# n64cart-1G.net
KiCad netlist of a schematic drawn in EAGLE
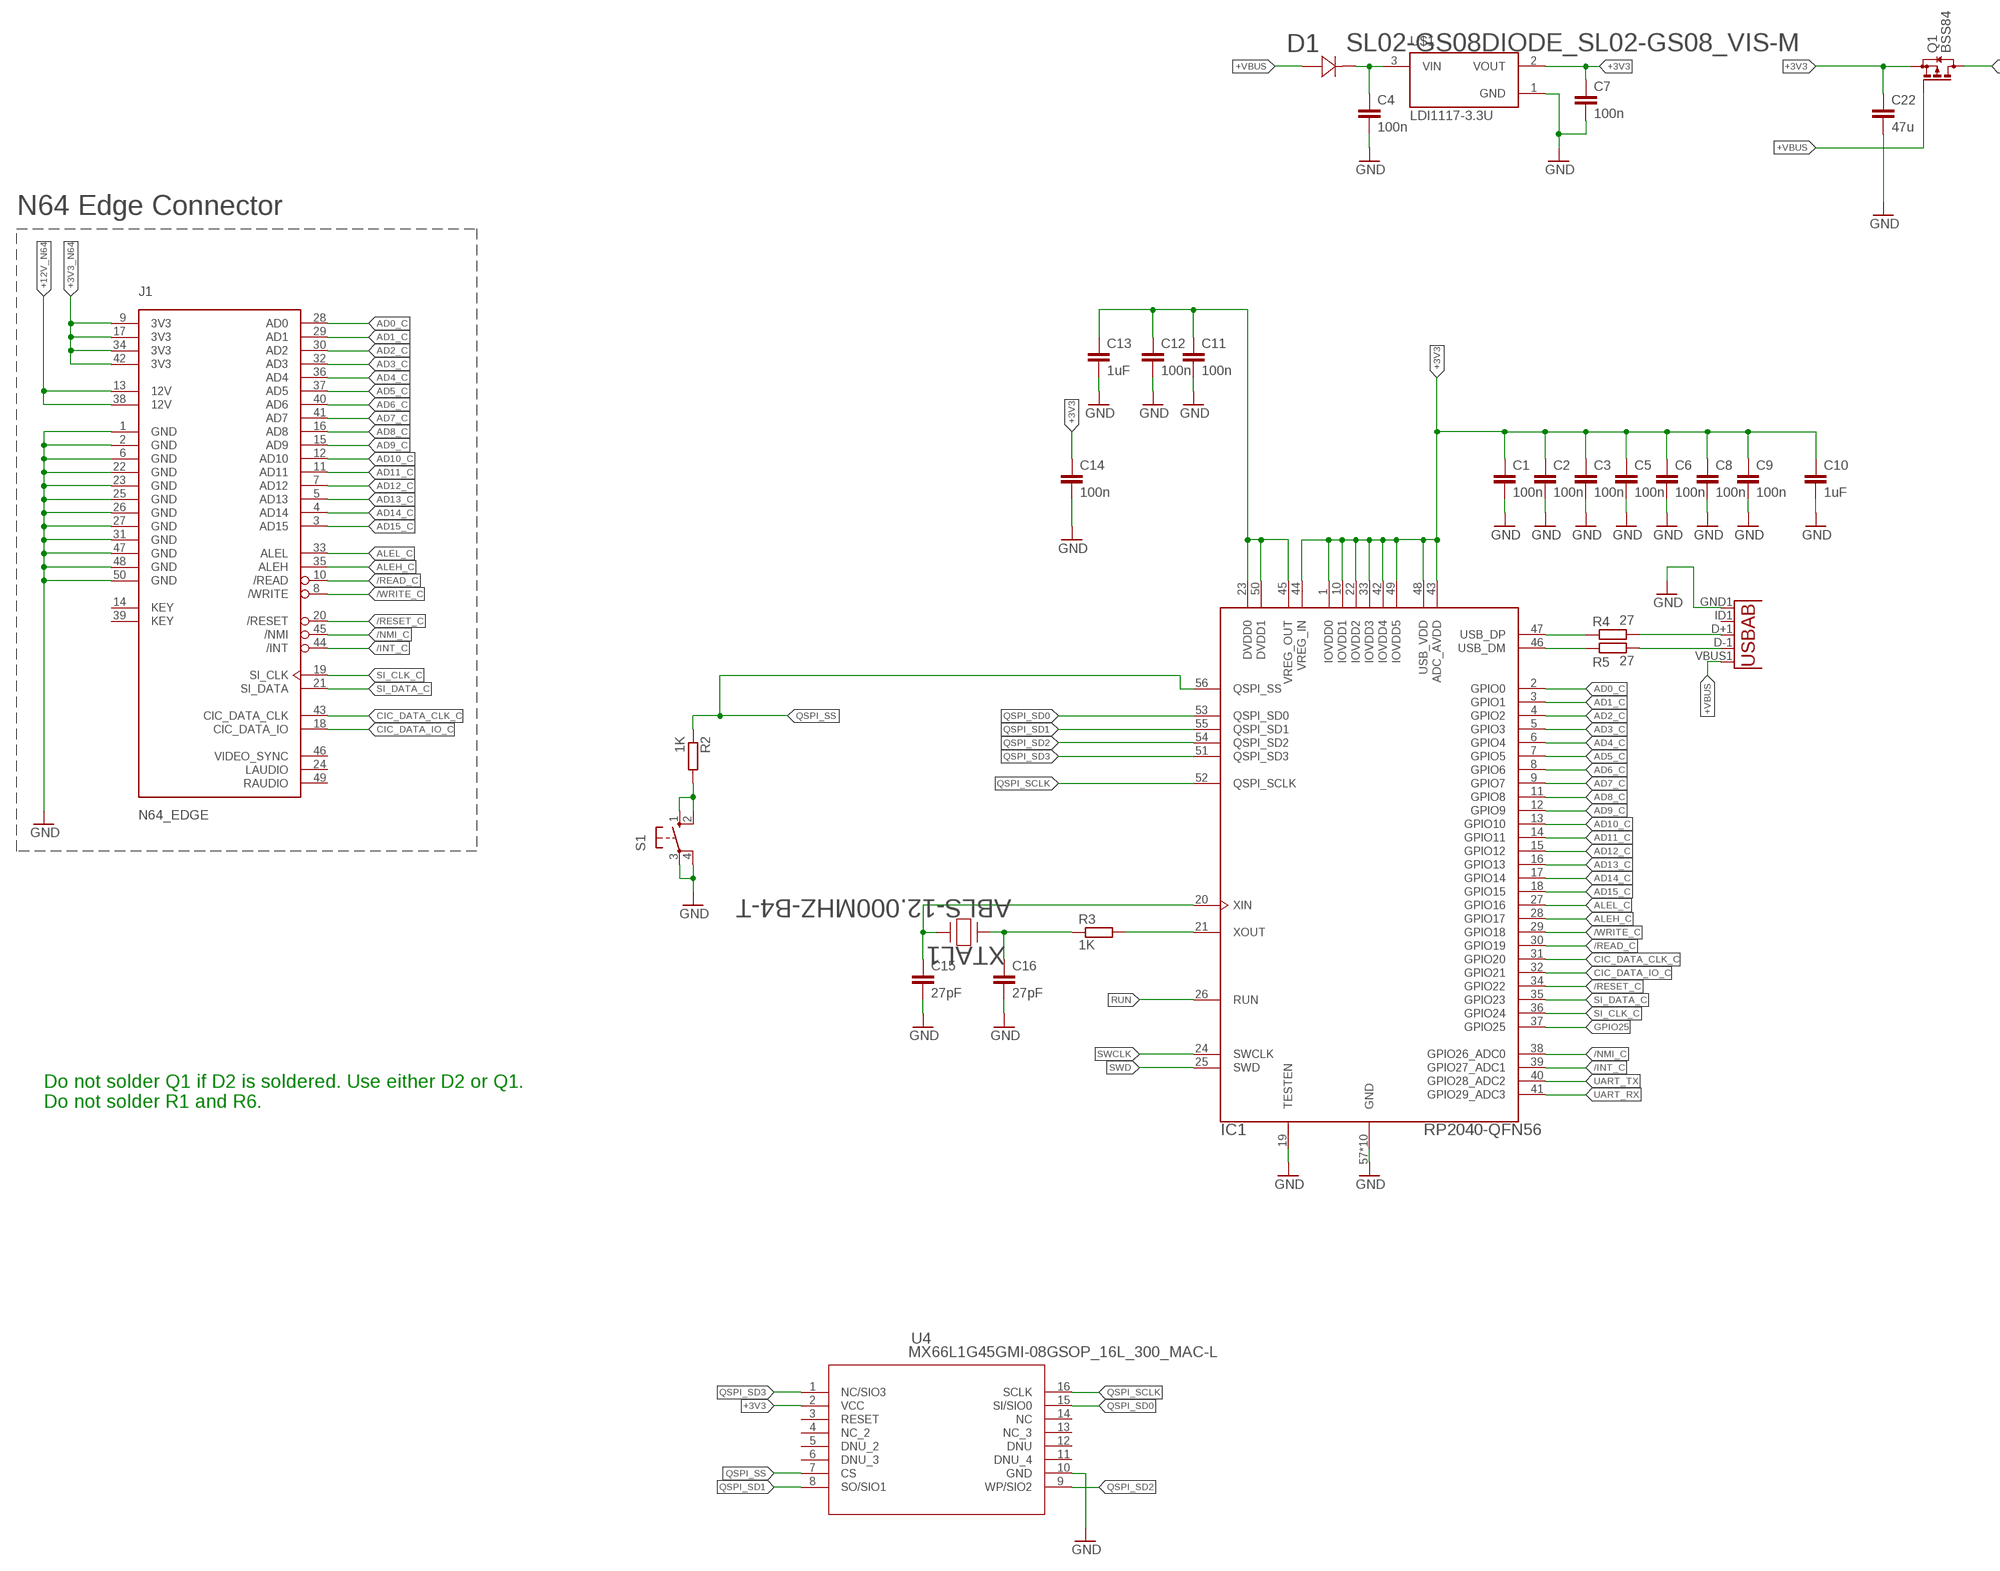
[diagram p0: schematic, sheet 1, part 1 of 2]
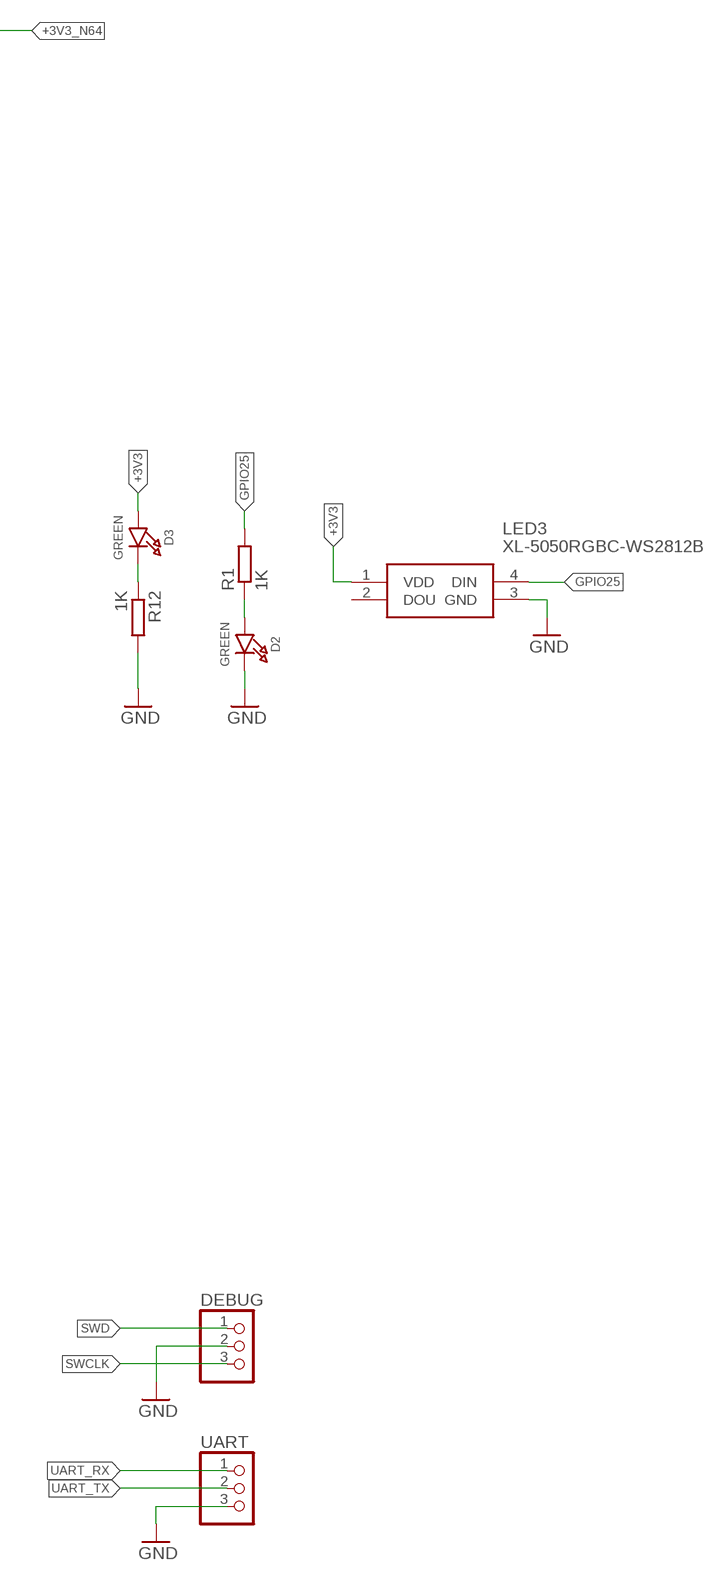
[diagram p1: schematic, sheet 1, part 2 of 2]

(export (version "E")
  (design (tool "Eeschema 10.0.6"))
  (components
    (comp (ref "C1")
      (value "100n")
      (footprint "eagle-import:C0402")
      (libsource (lib "eagle-import") (part "C-EUC0402"))
    )
    (comp (ref "C2")
      (value "100n")
      (footprint "eagle-import:C0402")
      (libsource (lib "eagle-import") (part "C-EUC0402"))
    )
    (comp (ref "C3")
      (value "100n")
      (footprint "eagle-import:C0402")
      (libsource (lib "eagle-import") (part "C-EUC0402"))
    )
    (comp (ref "C4")
      (value "100n")
      (footprint "eagle-import:C0603")
      (libsource (lib "eagle-import") (part "C-EUC0603"))
    )
    (comp (ref "C5")
      (value "100n")
      (footprint "eagle-import:C0402")
      (libsource (lib "eagle-import") (part "C-EUC0402"))
    )
    (comp (ref "C6")
      (value "100n")
      (footprint "eagle-import:C0402")
      (libsource (lib "eagle-import") (part "C-EUC0402"))
    )
    (comp (ref "C7")
      (value "100n")
      (footprint "eagle-import:C0603")
      (libsource (lib "eagle-import") (part "C-EUC0603"))
    )
    (comp (ref "C8")
      (value "100n")
      (footprint "eagle-import:C0402")
      (libsource (lib "eagle-import") (part "C-EUC0402"))
    )
    (comp (ref "C9")
      (value "100n")
      (footprint "eagle-import:C0402")
      (libsource (lib "eagle-import") (part "C-EUC0402"))
    )
    (comp (ref "C10")
      (value "1uF")
      (footprint "eagle-import:C0402")
      (libsource (lib "eagle-import") (part "C-EUC0402"))
    )
    (comp (ref "C11")
      (value "100n")
      (footprint "eagle-import:C0402")
      (libsource (lib "eagle-import") (part "C-EUC0402"))
    )
    (comp (ref "C12")
      (value "100n")
      (footprint "eagle-import:C0402")
      (libsource (lib "eagle-import") (part "C-EUC0402"))
    )
    (comp (ref "C13")
      (value "1uF")
      (footprint "eagle-import:C0402")
      (libsource (lib "eagle-import") (part "C-EUC0402"))
    )
    (comp (ref "C14")
      (value "100n")
      (footprint "eagle-import:C0402")
      (libsource (lib "eagle-import") (part "C-EUC0402"))
    )
    (comp (ref "C15")
      (value "27pF")
      (footprint "eagle-import:C0402")
      (libsource (lib "eagle-import") (part "C-EUC0402"))
    )
    (comp (ref "C16")
      (value "27pF")
      (footprint "eagle-import:C0402")
      (libsource (lib "eagle-import") (part "C-EUC0402"))
    )
    (comp (ref "C22")
      (value "47u")
      (footprint "eagle-import:C0805")
      (libsource (lib "eagle-import") (part "C-EUC0805"))
    )
    (comp (ref "D1")
      (value "SL02-GS08DIODE_SL02-GS08_VIS-M")
      (footprint "eagle-import:DIODE_SL02-GS08_VIS-M")
      (fields
        (field (name "MANUFACTURER_PART_NUMBER") "SL02-GS08")
        (field (name "COPYRIGHT") "Copyright (C) 2022 Ultra Librarian. All rights reserved.")
      )
      (libsource (lib "eagle-import") (part "SL02-GS08DIODE_SL02-GS08_VIS-M"))
    )
    (comp (ref "D2")
      (value "GREEN")
      (footprint "eagle-import:CHIPLED_0603_NOOUTLINE")
      (libsource (lib "eagle-import") (part "LED0603_NOOUTLINE"))
    )
    (comp (ref "D3")
      (value "GREEN")
      (footprint "eagle-import:CHIPLED_0603_NOOUTLINE")
      (libsource (lib "eagle-import") (part "LED0603_NOOUTLINE"))
    )
    (comp (ref "DEBUG")
      (value "PINHD-1X3")
      (footprint "eagle-import:1X03")
      (libsource (lib "eagle-import") (part "PINHD-1X3"))
    )
    (comp (ref "IC1")
      (value "RP2040-QFN56")
      (footprint "eagle-import:RP2040-QFN-56")
      (libsource (lib "eagle-import") (part "RP2040-QFN56"))
    )
    (comp (ref "J1")
      (value "N64_EDGE")
      (footprint "eagle-import:N64_EDGE")
      (libsource (lib "eagle-import") (part "N64_EDGE"))
    )
    (comp (ref "LED3")
      (value "XL-5050RGBC-WS2812B")
      (footprint "eagle-import:XL5050RGBCWS2812B")
      (libsource (lib "eagle-import") (part "XL-5050RGBC-WS2812B"))
    )
    (comp (ref "Q1")
      (value "BSS84")
      (footprint "eagle-import:SOT23")
      (libsource (lib "eagle-import") (part "BSS84"))
    )
    (comp (ref "R1")
      (value "1K")
      (footprint "eagle-import:R0603")
      (libsource (lib "eagle-import") (part "R-EU_R0603"))
    )
    (comp (ref "R2")
      (value "1K")
      (footprint "eagle-import:R0402")
      (libsource (lib "eagle-import") (part "R-EU_R0402"))
    )
    (comp (ref "R3")
      (value "1K")
      (footprint "eagle-import:R0402")
      (libsource (lib "eagle-import") (part "R-EU_R0402"))
    )
    (comp (ref "R4")
      (value "27")
      (footprint "eagle-import:R0402")
      (libsource (lib "eagle-import") (part "R-EU_R0402"))
    )
    (comp (ref "R5")
      (value "27")
      (footprint "eagle-import:R0402")
      (libsource (lib "eagle-import") (part "R-EU_R0402"))
    )
    (comp (ref "R12")
      (value "1K")
      (footprint "eagle-import:R0603")
      (libsource (lib "eagle-import") (part "R-EU_R0603"))
    )
    (comp (ref "S1")
      (value "10-XX")
      (footprint "eagle-import:B3F-10XX")
      (fields (field (name "MPN") "B3F-1000"))
      (libsource (lib "eagle-import") (part "10-XX"))
    )
    (comp (ref "U$1")
      (value "LDI1117-3.3U")
      (footprint "eagle-import:LDI1117-3.3U")
      (libsource (lib "eagle-import") (part "LDI1117-3.3U"))
    )
    (comp (ref "U2")
      (value "USB\"\"")
      (footprint "eagle-import:USB-MICRO-SMD")
      (libsource (lib "eagle-import") (part "USB{dblquote}{dblquote}"))
    )
    (comp (ref "U4")
      (value "MX66L1G45GMI-08GSOP_16L_300_MAC-L")
      (footprint "eagle-import:SOP_16L_300_MAC-L")
      (fields
        (field (name "MANUFACTURER_PART_NUMBER") "MX66L1G45GMI-08G")
        (field (name "COPYRIGHT") "Copyright (C) 2024 Ultra Librarian. All rights reserved.")
      )
      (libsource (lib "eagle-import") (part "MX66L1G45GMI-08GSOP_16L_300_MAC-L"))
    )
    (comp (ref "UART")
      (value "PINHD-1X3")
      (footprint "eagle-import:1X03")
      (libsource (lib "eagle-import") (part "PINHD-1X3"))
    )
    (comp (ref "XTAL1")
      (value "ABLS-12.000MHZ-B4-T")
      (footprint "eagle-import:XTAL_ABLS_ABR")
      (fields (field (name "COPYRIGHT") "Copyright (C) 2022 Ultra Librarian. All rights reserved."))
      (libsource (lib "eagle-import") (part "ABLS-12.000MHZ-B4-T"))
    )
  )
  (nets
    (net (code "1") (name "+3V3") (class "Default")
      (node (ref "C1") (pin "1") (pinfunction "1_1") (pintype "passive"))
      (node (ref "C10") (pin "1") (pinfunction "1_1") (pintype "passive"))
      (node (ref "C14") (pin "1") (pinfunction "1_1") (pintype "passive"))
      (node (ref "C2") (pin "1") (pinfunction "1_1") (pintype "passive"))
      (node (ref "C22") (pin "1") (pinfunction "1_1") (pintype "passive"))
      (node (ref "C3") (pin "1") (pinfunction "1_1") (pintype "passive"))
      (node (ref "C5") (pin "1") (pinfunction "1_1") (pintype "passive"))
      (node (ref "C6") (pin "1") (pinfunction "1_1") (pintype "passive"))
      (node (ref "C7") (pin "1") (pinfunction "1_1") (pintype "passive"))
      (node (ref "C8") (pin "1") (pinfunction "1_1") (pintype "passive"))
      (node (ref "C9") (pin "1") (pinfunction "1_1") (pintype "passive"))
      (node (ref "D3") (pin "A") (pinfunction "A_A") (pintype "passive"))
      (node (ref "IC1") (pin "1") (pinfunction "IOVDD0_1") (pintype "power_in"))
      (node (ref "IC1") (pin "10") (pinfunction "IOVDD1_10") (pintype "power_in"))
      (node (ref "IC1") (pin "22") (pinfunction "IOVDD2_22") (pintype "power_in"))
      (node (ref "IC1") (pin "33") (pinfunction "IOVDD3_33") (pintype "power_in"))
      (node (ref "IC1") (pin "42") (pinfunction "IOVDD4_42") (pintype "power_in"))
      (node (ref "IC1") (pin "43") (pinfunction "ADC_AVDD_43") (pintype "power_in"))
      (node (ref "IC1") (pin "44") (pinfunction "VREG_IN_44") (pintype "power_in"))
      (node (ref "IC1") (pin "48") (pinfunction "USB_VDD_48") (pintype "power_in"))
      (node (ref "IC1") (pin "49") (pinfunction "IOVDD5_49") (pintype "power_in"))
      (node (ref "LED3") (pin "1") (pinfunction "VDD_1") (pintype "bidirectional"))
      (node (ref "Q1") (pin "2") (pinfunction "S_2") (pintype "passive"))
      (node (ref "U$1") (pin "2") (pinfunction "VOUT_2") (pintype "output"))
      (node (ref "U4") (pin "2") (pinfunction "VCC_2") (pintype "power_in"))
    )
    (net (code "2") (name "+3V3_N64") (class "Default")
      (node (ref "J1") (pin "17") (pinfunction "3V3_17") (pintype "power_in"))
      (node (ref "J1") (pin "34") (pinfunction "3V3_34") (pintype "power_in"))
      (node (ref "J1") (pin "42") (pinfunction "3V3_42") (pintype "power_in"))
      (node (ref "J1") (pin "9") (pinfunction "3V3_9") (pintype "power_in"))
      (node (ref "Q1") (pin "3") (pinfunction "D_3") (pintype "passive"))
    )
    (net (code "3") (name "+12V_N64") (class "Default")
      (node (ref "J1") (pin "13") (pinfunction "12V_13") (pintype "power_in"))
      (node (ref "J1") (pin "38") (pinfunction "12V_38") (pintype "power_in"))
    )
    (net (code "4") (name "+VBUS") (class "Default")
      (node (ref "D1") (pin "2") (pinfunction "2_2") (pintype "passive"))
      (node (ref "Q1") (pin "1") (pinfunction "G_1") (pintype "passive"))
      (node (ref "U2") (pin "VBUS1") (pinfunction "VBUS_VBUS1") (pintype "bidirectional"))
    )
    (net (code "5") (name "AD0_C") (class "Default")
      (node (ref "IC1") (pin "2") (pinfunction "GPIO0_2") (pintype "bidirectional"))
      (node (ref "J1") (pin "28") (pinfunction "AD0_28") (pintype "bidirectional"))
    )
    (net (code "6") (name "AD1_C") (class "Default")
      (node (ref "IC1") (pin "3") (pinfunction "GPIO1_3") (pintype "bidirectional"))
      (node (ref "J1") (pin "29") (pinfunction "AD1_29") (pintype "bidirectional"))
    )
    (net (code "7") (name "AD2_C") (class "Default")
      (node (ref "IC1") (pin "4") (pinfunction "GPIO2_4") (pintype "bidirectional"))
      (node (ref "J1") (pin "30") (pinfunction "AD2_30") (pintype "bidirectional"))
    )
    (net (code "8") (name "AD3_C") (class "Default")
      (node (ref "IC1") (pin "5") (pinfunction "GPIO3_5") (pintype "bidirectional"))
      (node (ref "J1") (pin "32") (pinfunction "AD3_32") (pintype "bidirectional"))
    )
    (net (code "9") (name "AD4_C") (class "Default")
      (node (ref "IC1") (pin "6") (pinfunction "GPIO4_6") (pintype "bidirectional"))
      (node (ref "J1") (pin "36") (pinfunction "AD4_36") (pintype "bidirectional"))
    )
    (net (code "10") (name "AD5_C") (class "Default")
      (node (ref "IC1") (pin "7") (pinfunction "GPIO5_7") (pintype "bidirectional"))
      (node (ref "J1") (pin "37") (pinfunction "AD5_37") (pintype "bidirectional"))
    )
    (net (code "11") (name "AD6_C") (class "Default")
      (node (ref "IC1") (pin "8") (pinfunction "GPIO6_8") (pintype "bidirectional"))
      (node (ref "J1") (pin "40") (pinfunction "AD6_40") (pintype "bidirectional"))
    )
    (net (code "12") (name "AD7_C") (class "Default")
      (node (ref "IC1") (pin "9") (pinfunction "GPIO7_9") (pintype "bidirectional"))
      (node (ref "J1") (pin "41") (pinfunction "AD7_41") (pintype "bidirectional"))
    )
    (net (code "13") (name "AD8_C") (class "Default")
      (node (ref "IC1") (pin "11") (pinfunction "GPIO8_11") (pintype "bidirectional"))
      (node (ref "J1") (pin "16") (pinfunction "AD8_16") (pintype "bidirectional"))
    )
    (net (code "14") (name "AD9_C") (class "Default")
      (node (ref "IC1") (pin "12") (pinfunction "GPIO9_12") (pintype "bidirectional"))
      (node (ref "J1") (pin "15") (pinfunction "AD9_15") (pintype "bidirectional"))
    )
    (net (code "15") (name "AD10_C") (class "Default")
      (node (ref "IC1") (pin "13") (pinfunction "GPIO10_13") (pintype "bidirectional"))
      (node (ref "J1") (pin "12") (pinfunction "AD10_12") (pintype "bidirectional"))
    )
    (net (code "16") (name "AD11_C") (class "Default")
      (node (ref "IC1") (pin "14") (pinfunction "GPIO11_14") (pintype "bidirectional"))
      (node (ref "J1") (pin "11") (pinfunction "AD11_11") (pintype "bidirectional"))
    )
    (net (code "17") (name "AD12_C") (class "Default")
      (node (ref "IC1") (pin "15") (pinfunction "GPIO12_15") (pintype "bidirectional"))
      (node (ref "J1") (pin "7") (pinfunction "AD12_7") (pintype "bidirectional"))
    )
    (net (code "18") (name "AD13_C") (class "Default")
      (node (ref "IC1") (pin "16") (pinfunction "GPIO13_16") (pintype "bidirectional"))
      (node (ref "J1") (pin "5") (pinfunction "AD13_5") (pintype "bidirectional"))
    )
    (net (code "19") (name "AD14_C") (class "Default")
      (node (ref "IC1") (pin "17") (pinfunction "GPIO14_17") (pintype "bidirectional"))
      (node (ref "J1") (pin "4") (pinfunction "AD14_4") (pintype "bidirectional"))
    )
    (net (code "20") (name "AD15_C") (class "Default")
      (node (ref "IC1") (pin "18") (pinfunction "GPIO15_18") (pintype "bidirectional"))
      (node (ref "J1") (pin "3") (pinfunction "AD15_3") (pintype "bidirectional"))
    )
    (net (code "21") (name "ALEH_C") (class "Default")
      (node (ref "IC1") (pin "28") (pinfunction "GPIO17_28") (pintype "bidirectional"))
      (node (ref "J1") (pin "35") (pinfunction "ALEH_35") (pintype "output"))
    )
    (net (code "22") (name "ALEL_C") (class "Default")
      (node (ref "IC1") (pin "27") (pinfunction "GPIO16_27") (pintype "bidirectional"))
      (node (ref "J1") (pin "33") (pinfunction "ALEL_33") (pintype "output"))
    )
    (net (code "23") (name "CIC_DATA_CLK_C") (class "Default")
      (node (ref "IC1") (pin "31") (pinfunction "GPIO20_31") (pintype "bidirectional"))
      (node (ref "J1") (pin "43") (pinfunction "CIC_DATA_CLK_43") (pintype "output"))
    )
    (net (code "24") (name "CIC_DATA_IO_C") (class "Default")
      (node (ref "IC1") (pin "32") (pinfunction "GPIO21_32") (pintype "bidirectional"))
      (node (ref "J1") (pin "18") (pinfunction "CIC_DATA_IO_18") (pintype "bidirectional"))
    )
    (net (code "25") (name "GND") (class "Default")
      (node (ref "C1") (pin "2") (pinfunction "2_2") (pintype "passive"))
      (node (ref "C10") (pin "2") (pinfunction "2_2") (pintype "passive"))
      (node (ref "C11") (pin "2") (pinfunction "2_2") (pintype "passive"))
      (node (ref "C12") (pin "2") (pinfunction "2_2") (pintype "passive"))
      (node (ref "C13") (pin "2") (pinfunction "2_2") (pintype "passive"))
      (node (ref "C14") (pin "2") (pinfunction "2_2") (pintype "passive"))
      (node (ref "C15") (pin "2") (pinfunction "2_2") (pintype "passive"))
      (node (ref "C16") (pin "2") (pinfunction "2_2") (pintype "passive"))
      (node (ref "C2") (pin "2") (pinfunction "2_2") (pintype "passive"))
      (node (ref "C22") (pin "2") (pinfunction "2_2") (pintype "passive"))
      (node (ref "C3") (pin "2") (pinfunction "2_2") (pintype "passive"))
      (node (ref "C4") (pin "2") (pinfunction "2_2") (pintype "passive"))
      (node (ref "C5") (pin "2") (pinfunction "2_2") (pintype "passive"))
      (node (ref "C6") (pin "2") (pinfunction "2_2") (pintype "passive"))
      (node (ref "C7") (pin "2") (pinfunction "2_2") (pintype "passive"))
      (node (ref "C8") (pin "2") (pinfunction "2_2") (pintype "passive"))
      (node (ref "C9") (pin "2") (pinfunction "2_2") (pintype "passive"))
      (node (ref "D2") (pin "C") (pinfunction "C_C") (pintype "passive"))
      (node (ref "DEBUG") (pin "2") (pinfunction "2_2") (pintype "passive"))
      (node (ref "IC1") (pin "19") (pinfunction "TESTEN_19") (pintype "passive"))
      (node (ref "IC1") (pin "57") (pinfunction "GND_57") (pintype "power_in"))
      (node (ref "IC1") (pin "58") (pinfunction "GND_58") (pintype "power_in"))
      (node (ref "IC1") (pin "59") (pinfunction "GND_59") (pintype "power_in"))
      (node (ref "IC1") (pin "60") (pinfunction "GND_60") (pintype "power_in"))
      (node (ref "IC1") (pin "61") (pinfunction "GND_61") (pintype "power_in"))
      (node (ref "IC1") (pin "62") (pinfunction "GND_62") (pintype "power_in"))
      (node (ref "IC1") (pin "63") (pinfunction "GND_63") (pintype "power_in"))
      (node (ref "IC1") (pin "64") (pinfunction "GND_64") (pintype "power_in"))
      (node (ref "IC1") (pin "65") (pinfunction "GND_65") (pintype "power_in"))
      (node (ref "IC1") (pin "66") (pinfunction "GND_66") (pintype "power_in"))
      (node (ref "J1") (pin "1") (pinfunction "GND_1") (pintype "power_in"))
      (node (ref "J1") (pin "2") (pinfunction "GND_2") (pintype "power_in"))
      (node (ref "J1") (pin "22") (pinfunction "GND_22") (pintype "power_in"))
      (node (ref "J1") (pin "23") (pinfunction "GND_23") (pintype "power_in"))
      (node (ref "J1") (pin "25") (pinfunction "GND_25") (pintype "power_in"))
      (node (ref "J1") (pin "26") (pinfunction "GND_26") (pintype "power_in"))
      (node (ref "J1") (pin "27") (pinfunction "GND_27") (pintype "power_in"))
      (node (ref "J1") (pin "31") (pinfunction "GND_31") (pintype "power_in"))
      (node (ref "J1") (pin "47") (pinfunction "GND_47") (pintype "power_in"))
      (node (ref "J1") (pin "48") (pinfunction "GND_48") (pintype "power_in"))
      (node (ref "J1") (pin "50") (pinfunction "GND_50") (pintype "power_in"))
      (node (ref "J1") (pin "6") (pinfunction "GND_6") (pintype "power_in"))
      (node (ref "LED3") (pin "3") (pinfunction "GND_3") (pintype "bidirectional"))
      (node (ref "R12") (pin "2") (pinfunction "2_2") (pintype "passive"))
      (node (ref "S1") (pin "3") (pinfunction "P_3") (pintype "passive"))
      (node (ref "S1") (pin "4") (pinfunction "P1_4") (pintype "passive"))
      (node (ref "U$1") (pin "1") (pinfunction "GND_1") (pintype "power_in"))
      (node (ref "U2") (pin "GND1") (pinfunction "GND_GND1") (pintype "bidirectional"))
      (node (ref "U4") (pin "10") (pinfunction "GND_10") (pintype "passive"))
      (node (ref "UART") (pin "3") (pinfunction "3_3") (pintype "passive"))
    )
    (net (code "26") (name "GPIO25") (class "Default")
      (node (ref "IC1") (pin "37") (pinfunction "GPIO25_37") (pintype "bidirectional"))
      (node (ref "LED3") (pin "4") (pinfunction "DIN_4") (pintype "bidirectional"))
      (node (ref "R1") (pin "2") (pinfunction "2_2") (pintype "passive"))
    )
    (net (code "27") (name "Net-(C16-Pad1)") (class "Default")
      (node (ref "C16") (pin "1") (pinfunction "1_1") (pintype "passive"))
      (node (ref "R3") (pin "1") (pinfunction "1_1") (pintype "passive"))
      (node (ref "XTAL1") (pin "1") (pinfunction "1_1") (pintype "passive"))
    )
    (net (code "28") (name "Net-(D2-PadA)") (class "Default")
      (node (ref "D2") (pin "A") (pinfunction "A_A") (pintype "passive"))
      (node (ref "R1") (pin "1") (pinfunction "1_1") (pintype "passive"))
    )
    (net (code "29") (name "Net-(D3-PadC)") (class "Default")
      (node (ref "D3") (pin "C") (pinfunction "C_C") (pintype "passive"))
      (node (ref "R12") (pin "1") (pinfunction "1_1") (pintype "passive"))
    )
    (net (code "30") (name "Net-(IC1-DVDD0)") (class "Default")
      (node (ref "C11") (pin "1") (pinfunction "1_1") (pintype "passive"))
      (node (ref "C12") (pin "1") (pinfunction "1_1") (pintype "passive"))
      (node (ref "C13") (pin "1") (pinfunction "1_1") (pintype "passive"))
      (node (ref "IC1") (pin "23") (pinfunction "DVDD0_23") (pintype "power_in"))
      (node (ref "IC1") (pin "45") (pinfunction "VREG_OUT_45") (pintype "power_in"))
      (node (ref "IC1") (pin "50") (pinfunction "DVDD1_50") (pintype "power_in"))
    )
    (net (code "31") (name "Net-(IC1-USB_DM)") (class "Default")
      (node (ref "IC1") (pin "46") (pinfunction "USB_DM_46") (pintype "bidirectional"))
      (node (ref "R5") (pin "1") (pinfunction "1_1") (pintype "passive"))
    )
    (net (code "32") (name "Net-(IC1-USB_DP)") (class "Default")
      (node (ref "IC1") (pin "47") (pinfunction "USB_DP_47") (pintype "bidirectional"))
      (node (ref "R4") (pin "1") (pinfunction "1_1") (pintype "passive"))
    )
    (net (code "33") (name "Net-(IC1-XIN)") (class "Default")
      (node (ref "C15") (pin "1") (pinfunction "1_1") (pintype "passive"))
      (node (ref "IC1") (pin "20") (pinfunction "XIN_20") (pintype "input"))
      (node (ref "XTAL1") (pin "2") (pinfunction "2_2") (pintype "passive"))
    )
    (net (code "34") (name "Net-(IC1-XOUT)") (class "Default")
      (node (ref "IC1") (pin "21") (pinfunction "XOUT_21") (pintype "passive"))
      (node (ref "R3") (pin "2") (pinfunction "2_2") (pintype "passive"))
    )
    (net (code "35") (name "Net-(S1-S)") (class "Default")
      (node (ref "R2") (pin "2") (pinfunction "2_2") (pintype "passive"))
      (node (ref "S1") (pin "1") (pinfunction "S_1") (pintype "passive"))
      (node (ref "S1") (pin "2") (pinfunction "S1_2") (pintype "passive"))
    )
    (net (code "36") (name "Net-(U$1-VIN)") (class "Default")
      (node (ref "C4") (pin "1") (pinfunction "1_1") (pintype "passive"))
      (node (ref "D1") (pin "1") (pinfunction "1_1") (pintype "passive"))
      (node (ref "U$1") (pin "3") (pinfunction "VIN_3") (pintype "input"))
    )
    (net (code "37") (name "Net-(U2-D+)") (class "Default")
      (node (ref "R4") (pin "2") (pinfunction "2_2") (pintype "passive"))
      (node (ref "U2") (pin "D+1") (pinfunction "D+_D+1") (pintype "bidirectional"))
    )
    (net (code "38") (name "Net-(U2-D-)") (class "Default")
      (node (ref "R5") (pin "2") (pinfunction "2_2") (pintype "passive"))
      (node (ref "U2") (pin "D-1") (pinfunction "D-_D-1") (pintype "bidirectional"))
    )
    (net (code "39") (name "QSPI_SCLK") (class "Default")
      (node (ref "IC1") (pin "52") (pinfunction "QSPI_SCLK_52") (pintype "output"))
      (node (ref "U4") (pin "16") (pinfunction "SCLK_16") (pintype "input"))
    )
    (net (code "40") (name "QSPI_SD0") (class "Default")
      (node (ref "IC1") (pin "53") (pinfunction "QSPI_SD0_53") (pintype "bidirectional"))
      (node (ref "U4") (pin "15") (pinfunction "SI/SIO0_15") (pintype "bidirectional"))
    )
    (net (code "41") (name "QSPI_SD1") (class "Default")
      (node (ref "IC1") (pin "55") (pinfunction "QSPI_SD1_55") (pintype "bidirectional"))
      (node (ref "U4") (pin "8") (pinfunction "SO/SIO1_8") (pintype "bidirectional"))
    )
    (net (code "42") (name "QSPI_SD2") (class "Default")
      (node (ref "IC1") (pin "54") (pinfunction "QSPI_SD2_54") (pintype "bidirectional"))
      (node (ref "U4") (pin "9") (pinfunction "WP/SIO2_9") (pintype "bidirectional"))
    )
    (net (code "43") (name "QSPI_SD3") (class "Default")
      (node (ref "IC1") (pin "51") (pinfunction "QSPI_SD3_51") (pintype "bidirectional"))
      (node (ref "U4") (pin "1") (pinfunction "NC/SIO3_1") (pintype "passive"))
    )
    (net (code "44") (name "QSPI_SS") (class "Default")
      (node (ref "IC1") (pin "56") (pinfunction "QSPI_SS_56") (pintype "bidirectional"))
      (node (ref "R2") (pin "1") (pinfunction "1_1") (pintype "passive"))
      (node (ref "U4") (pin "7") (pinfunction "CS_7") (pintype "input"))
    )
    (net (code "45") (name "RUN") (class "Default")
      (node (ref "IC1") (pin "26") (pinfunction "RUN_26") (pintype "input"))
    )
    (net (code "46") (name "SI_CLK_C") (class "Default")
      (node (ref "IC1") (pin "36") (pinfunction "GPIO24_36") (pintype "bidirectional"))
      (node (ref "J1") (pin "19") (pinfunction "SI_CLK_19") (pintype "output"))
    )
    (net (code "47") (name "SI_DATA_C") (class "Default")
      (node (ref "IC1") (pin "35") (pinfunction "GPIO23_35") (pintype "bidirectional"))
      (node (ref "J1") (pin "21") (pinfunction "SI_DATA_21") (pintype "bidirectional"))
    )
    (net (code "48") (name "SWCLK") (class "Default")
      (node (ref "DEBUG") (pin "3") (pinfunction "3_3") (pintype "passive"))
      (node (ref "IC1") (pin "24") (pinfunction "SWCLK_24") (pintype "output"))
    )
    (net (code "49") (name "SWD") (class "Default")
      (node (ref "DEBUG") (pin "1") (pinfunction "1_1") (pintype "passive"))
      (node (ref "IC1") (pin "25") (pinfunction "SWD_25") (pintype "bidirectional"))
    )
    (net (code "50") (name "UART_RX") (class "Default")
      (node (ref "IC1") (pin "41") (pinfunction "GPIO29_ADC3_41") (pintype "bidirectional"))
      (node (ref "UART") (pin "1") (pinfunction "1_1") (pintype "passive"))
    )
    (net (code "51") (name "UART_TX") (class "Default")
      (node (ref "IC1") (pin "40") (pinfunction "GPIO28_ADC2_40") (pintype "bidirectional"))
      (node (ref "UART") (pin "2") (pinfunction "2_2") (pintype "passive"))
    )
    (net (code "52") (name "unconnected-(J1-KEY-Pad14)") (class "Default")
      (node (ref "J1") (pin "14") (pinfunction "KEY_14") (pintype "no_connect"))
    )
    (net (code "53") (name "unconnected-(J1-KEY-Pad39)") (class "Default")
      (node (ref "J1") (pin "39") (pinfunction "KEY_39") (pintype "no_connect"))
    )
    (net (code "54") (name "unconnected-(J1-LAUDIO-Pad24)") (class "Default")
      (node (ref "J1") (pin "24") (pinfunction "LAUDIO_24") (pintype "input"))
    )
    (net (code "55") (name "unconnected-(J1-RAUDIO-Pad49)") (class "Default")
      (node (ref "J1") (pin "49") (pinfunction "RAUDIO_49") (pintype "input"))
    )
    (net (code "56") (name "unconnected-(J1-VIDEO_SYNC-Pad46)") (class "Default")
      (node (ref "J1") (pin "46") (pinfunction "VIDEO_SYNC_46") (pintype "output"))
    )
    (net (code "57") (name "unconnected-(LED3-DOU-Pad2)") (class "Default")
      (node (ref "LED3") (pin "2") (pinfunction "DOU_2") (pintype "bidirectional"))
    )
    (net (code "58") (name "unconnected-(U2-USBID-PadID1)") (class "Default")
      (node (ref "U2") (pin "ID1") (pinfunction "USBID_ID1") (pintype "bidirectional"))
    )
    (net (code "59") (name "unconnected-(U4-DNU-Pad12)") (class "Default")
      (node (ref "U4") (pin "12") (pinfunction "DNU_12") (pintype "no_connect"))
    )
    (net (code "60") (name "unconnected-(U4-DNU_2-Pad5)") (class "Default")
      (node (ref "U4") (pin "5") (pinfunction "DNU_2_5") (pintype "no_connect"))
    )
    (net (code "61") (name "unconnected-(U4-DNU_3-Pad6)") (class "Default")
      (node (ref "U4") (pin "6") (pinfunction "DNU_3_6") (pintype "no_connect"))
    )
    (net (code "62") (name "unconnected-(U4-DNU_4-Pad11)") (class "Default")
      (node (ref "U4") (pin "11") (pinfunction "DNU_4_11") (pintype "no_connect"))
    )
    (net (code "63") (name "unconnected-(U4-NC-Pad14)") (class "Default")
      (node (ref "U4") (pin "14") (pinfunction "NC_14") (pintype "no_connect"))
    )
    (net (code "64") (name "unconnected-(U4-NC_2-Pad4)") (class "Default")
      (node (ref "U4") (pin "4") (pinfunction "NC_2_4") (pintype "no_connect"))
    )
    (net (code "65") (name "unconnected-(U4-NC_3-Pad13)") (class "Default")
      (node (ref "U4") (pin "13") (pinfunction "NC_3_13") (pintype "no_connect"))
    )
    (net (code "66") (name "unconnected-(U4-RESET-Pad3)") (class "Default")
      (node (ref "U4") (pin "3") (pinfunction "RESET_3") (pintype "input"))
    )
    (net (code "67") (name "{slash}INT_C") (class "Default")
      (node (ref "IC1") (pin "39") (pinfunction "GPIO27_ADC1_39") (pintype "bidirectional"))
      (node (ref "J1") (pin "44") (pinfunction "/INT_44") (pintype "input"))
    )
    (net (code "68") (name "{slash}NMI_C") (class "Default")
      (node (ref "IC1") (pin "38") (pinfunction "GPIO26_ADC0_38") (pintype "bidirectional"))
      (node (ref "J1") (pin "45") (pinfunction "/NMI_45") (pintype "output"))
    )
    (net (code "69") (name "{slash}READ_C") (class "Default")
      (node (ref "IC1") (pin "30") (pinfunction "GPIO19_30") (pintype "bidirectional"))
      (node (ref "J1") (pin "10") (pinfunction "/READ_10") (pintype "output"))
    )
    (net (code "70") (name "{slash}RESET_C") (class "Default")
      (node (ref "IC1") (pin "34") (pinfunction "GPIO22_34") (pintype "bidirectional"))
      (node (ref "J1") (pin "20") (pinfunction "/RESET_20") (pintype "output"))
    )
    (net (code "71") (name "{slash}WRITE_C") (class "Default")
      (node (ref "IC1") (pin "29") (pinfunction "GPIO18_29") (pintype "bidirectional"))
      (node (ref "J1") (pin "8") (pinfunction "/WRITE_8") (pintype "output"))
    )
  )
)
